# Status_LED.net
KiCad netlist of a schematic drawn in Altium Designer
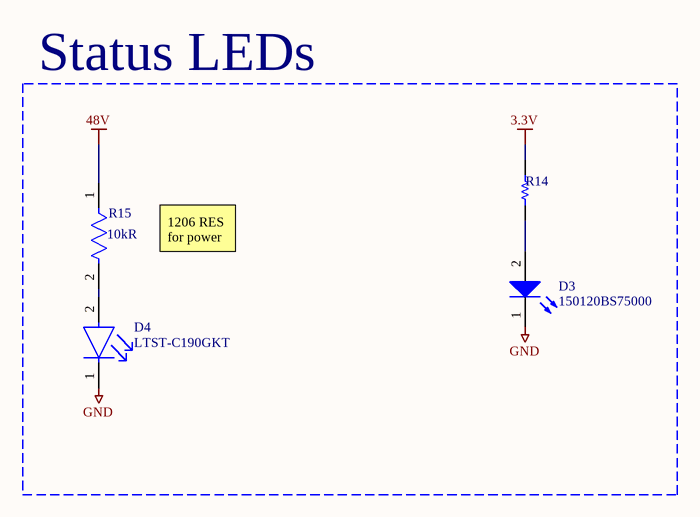
[diagram p0: Status_LED.SchDoc]

(export (version "E")
  (design (tool "Eeschema 10.0.6"))
  (components
    (comp (ref "D3")
      (value "150120BS75000")
      (footprint "WL-SMCW_1206_150120xx75000")
      (description "WL-SMCW SMT Mono-Color Chip LED Waterclear")
      (libsource (lib "Altium Content Vault") (part "LED_Blue_2A-1K"))
    )
    (comp (ref "D4")
      (value "LTST-C190GKT")
      (footprint "FP-LTST-C190GKT-MFG")
      (description "LED GREEN CLEAR CHIP SMD")
      (fields (field (name "VOLTAGE") "2V"))
      (libsource (lib "Altium Content Vault") (part "8706943c75ba83719d021d2fdc84c58"))
    )
    (comp (ref "R14")
      (value "ERA3AEB301V")
      (footprint "RESC1608X55X30LL20T20")
      (fields (field (name "MANUFACTURER") "Panasonic"))
      (libsource (lib "Altium Content Vault") (part "RES"))
    )
    (comp (ref "R15")
      (value "RK73H2BTTDD1002F")
      (footprint "FP-RK73H2B-IPC_C")
      (description "10kΩ ±1% 0.25W Chip Resistor 1206 Thick Film AEC-Q200 Qualified")
      (fields (field (name "RESISTANCE") "10kR") (field (name "TOLERANCE") "1%"))
      (libsource (lib "Altium Content Vault") (part "1029c3af85768c4190bb7ad29bc67b5"))
    )
  )
  (nets
    (net (code "1") (name "3.3V") (class "Default")
      (node (ref "R14") (pin "1") (pinfunction "1_1") (pintype "passive"))
    )
    (net (code "2") (name "48V") (class "Default")
      (node (ref "R15") (pin "1") (pinfunction "1_1") (pintype "passive"))
    )
    (net (code "3") (name "GND") (class "Default")
      (node (ref "D3") (pin "1") (pinfunction "K_1") (pintype "passive"))
      (node (ref "D4") (pin "1") (pinfunction "C_1") (pintype "passive"))
    )
    (net (code "4") (name "Net-(D3-A)") (class "Default")
      (node (ref "D3") (pin "2") (pinfunction "A_2") (pintype "passive"))
      (node (ref "R14") (pin "2") (pinfunction "2_2") (pintype "passive"))
    )
    (net (code "5") (name "Net-(D4-A)") (class "Default")
      (node (ref "D4") (pin "2") (pinfunction "A_2") (pintype "passive"))
      (node (ref "R15") (pin "2") (pinfunction "2_2") (pintype "passive"))
    )
  )
)
